# pre_pcb_new_pcb_design.net
KiCad netlist of a schematic drawn in EasyEDA Pro
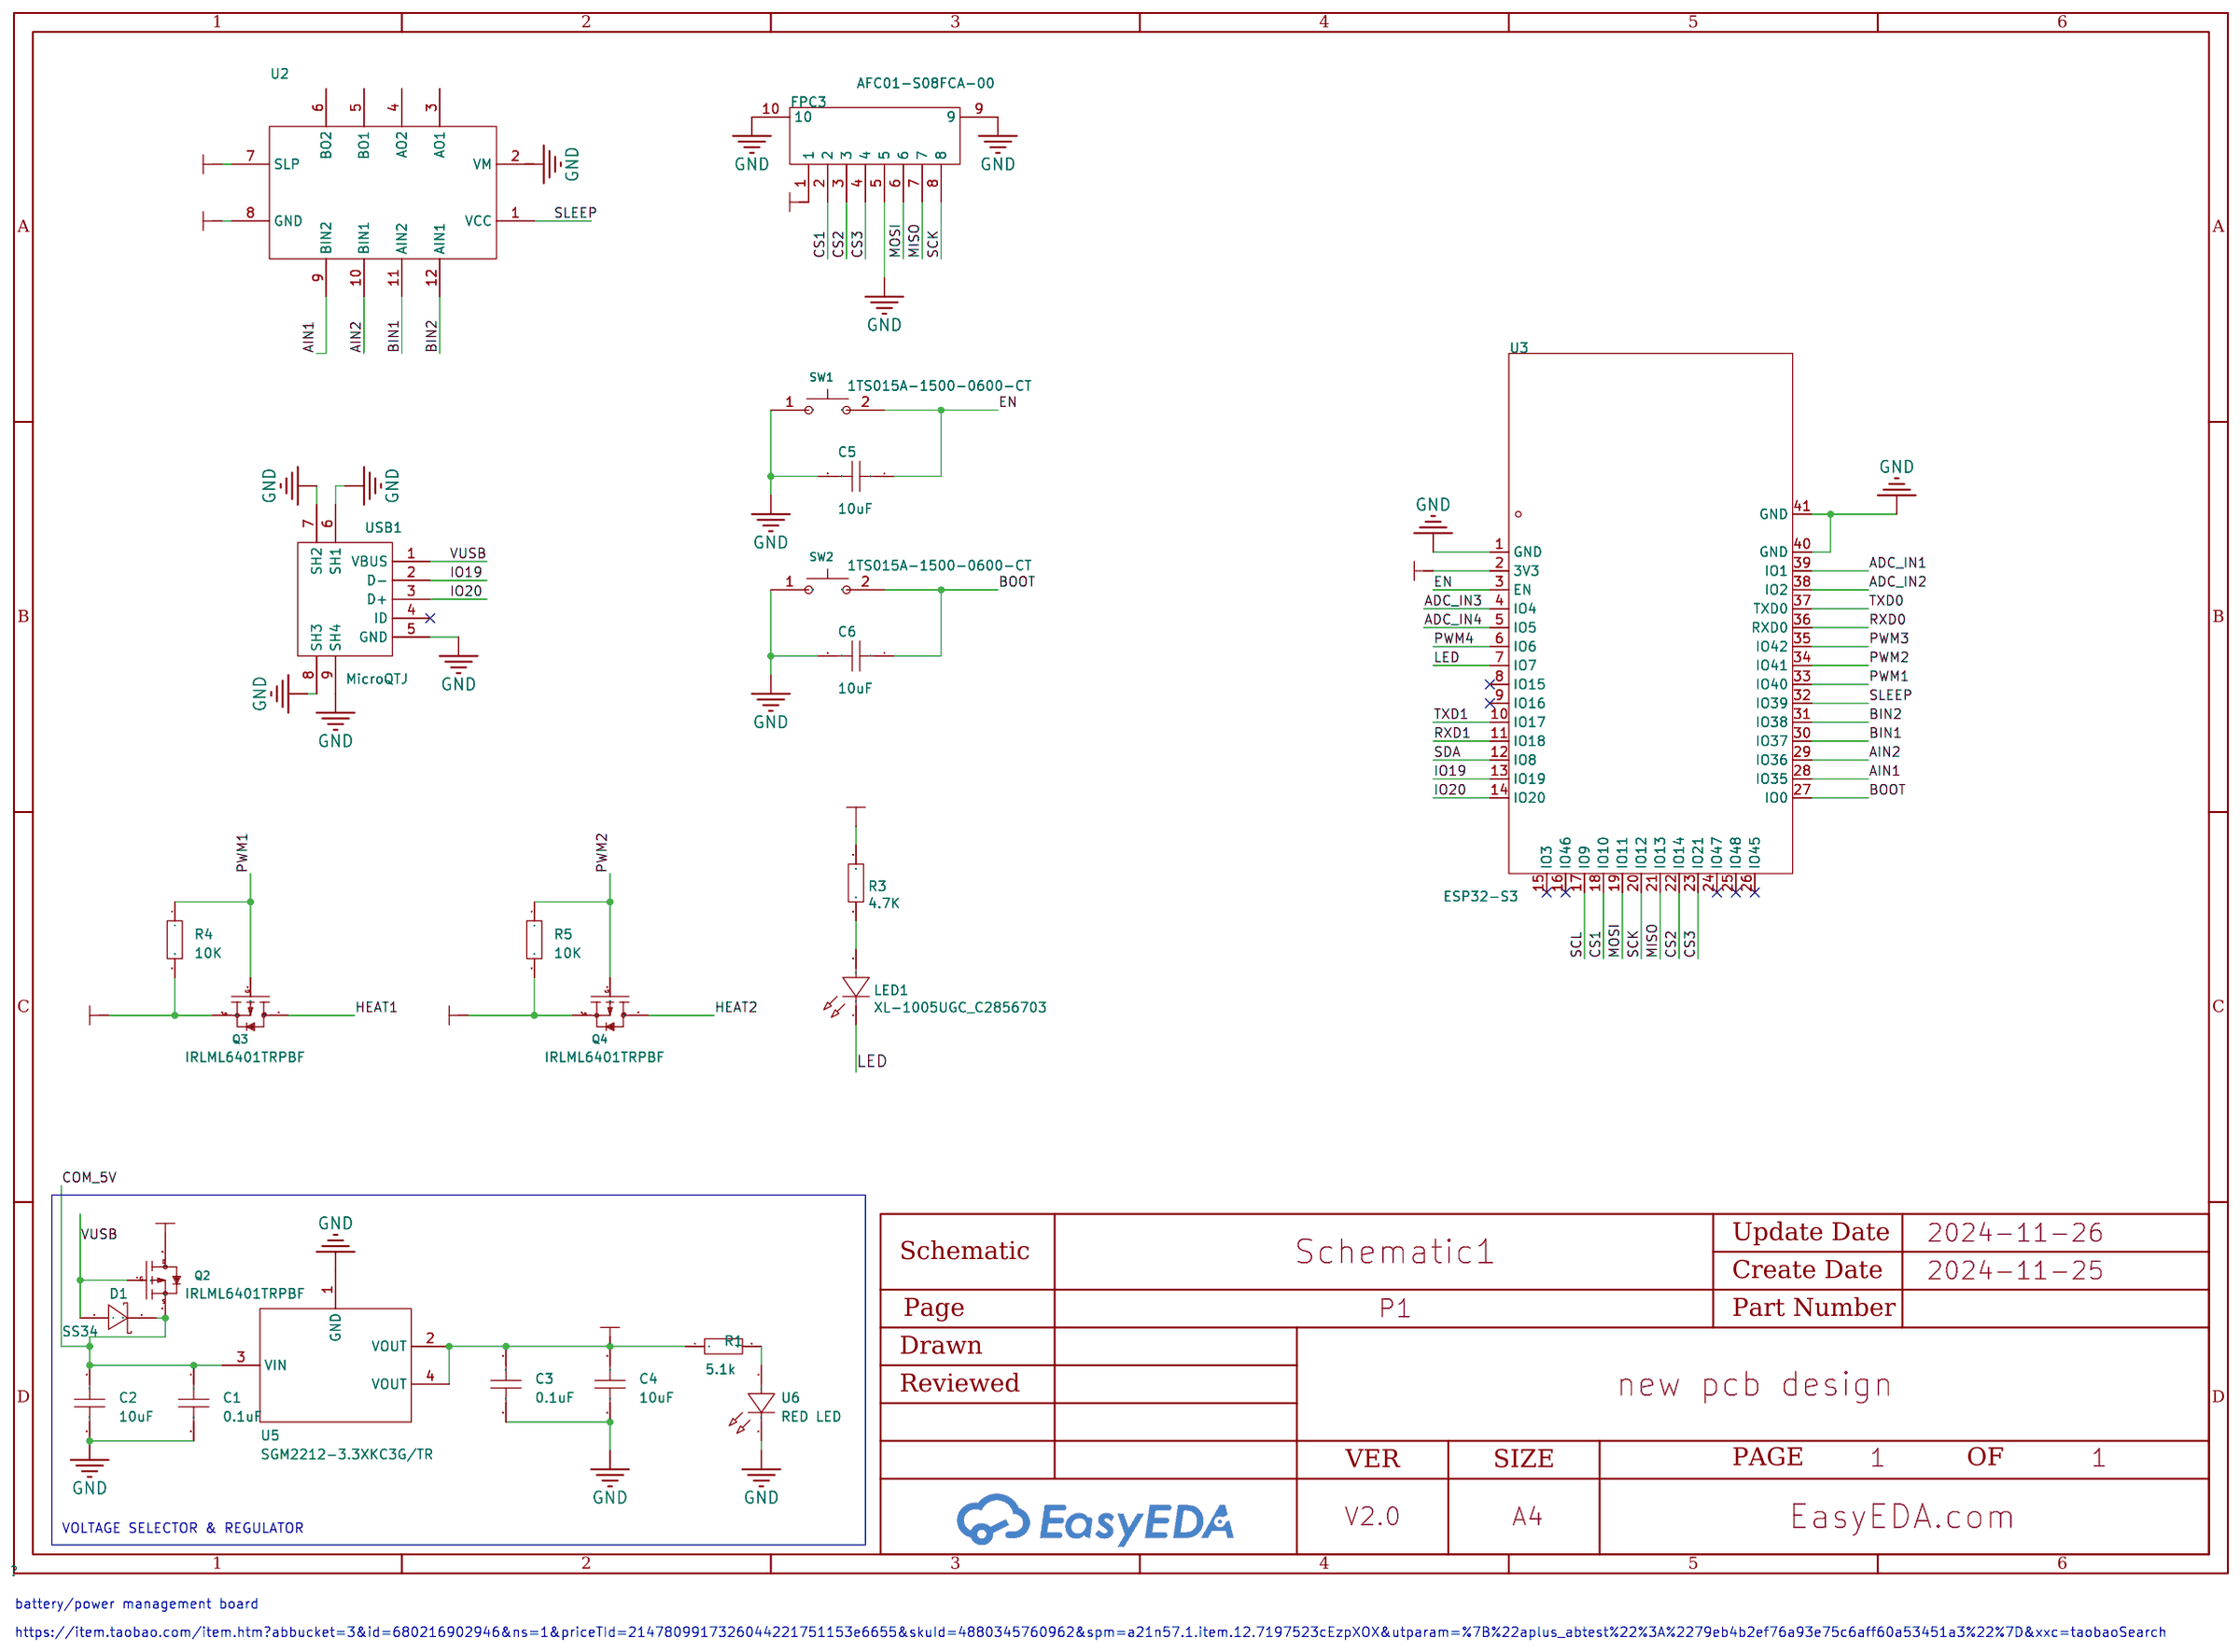
[diagram p0: schematic sheet]

(export (version "E")
  (design (tool "Eeschema 10.0.6"))
  (components
    (comp (ref "C1")
      (value "0.1uF")
      (footprint "easyedapro:C0603")
      (libsource (lib "easyedapro") (part "CAP"))
    )
    (comp (ref "C2")
      (value "10uF")
      (footprint "easyedapro:C0603")
      (libsource (lib "easyedapro") (part "CAP"))
    )
    (comp (ref "C3")
      (value "0.1uF")
      (footprint "easyedapro:C0603")
      (libsource (lib "easyedapro") (part "CAP"))
    )
    (comp (ref "C4")
      (value "10uF")
      (footprint "easyedapro:C0603")
      (libsource (lib "easyedapro") (part "CAP"))
    )
    (comp (ref "C5")
      (value "10uF")
      (footprint "easyedapro:C0603")
      (libsource (lib "easyedapro") (part "CAP"))
    )
    (comp (ref "C6")
      (value "10uF")
      (footprint "easyedapro:C0603")
      (libsource (lib "easyedapro") (part "CAP"))
    )
    (comp (ref "D1")
      (value "SS34")
      (footprint "easyedapro:SMC_L6.9-W5.9-LS7.9-RD")
      (description "Forward Voltage (Vf@If):500mV@3A Reverse Voltage (Vr):40V Average Rectified Current (Io):3A")
      (libsource (lib "easyedapro") (part "SS34_C169162"))
    )
    (comp (ref "FPC3")
      (value "AFC01-S08FCA-00")
      (footprint "easyedapro:FPC-SMD_P0.50-8P_FGS-XJ-H2.0")
      (fields (field (name "Manufacturer") "JS(钜硕电子)"))
      (libsource (lib "easyedapro") (part "AFC01-S08FCA-00"))
    )
    (comp (ref "LED1")
      (value "XL-1005UGC_C2856703")
      (footprint "easyedapro:LED0402-RD_GREEN")
      (fields (field (name "Manufacturer Part") "XL-1005UGC") (field (name "Manufacturer") "XINGLIGHT(成兴光)"))
      (libsource (lib "easyedapro") (part "XL-1005UGC_C2856703"))
    )
    (comp (ref "Q2")
      (value "IRLML6401TRPBF")
      (footprint "easyedapro:SOT-23-3_L2.9-W1.3-P1.90-LS2.4-BR")
      (fields (field (name "Manufacturer") "TECH PUBLIC(台舟)"))
      (libsource (lib "easyedapro") (part "IRLML6401TRPBF_C5182042"))
    )
    (comp (ref "Q3")
      (value "IRLML6401TRPBF")
      (footprint "easyedapro:SOT-23-3_L2.9-W1.3-P1.90-LS2.4-BR")
      (fields (field (name "Manufacturer") "TECH PUBLIC(台舟)"))
      (libsource (lib "easyedapro") (part "IRLML6401TRPBF_C5182042"))
    )
    (comp (ref "Q4")
      (value "IRLML6401TRPBF")
      (footprint "easyedapro:SOT-23-3_L2.9-W1.3-P1.90-LS2.4-BR")
      (fields (field (name "Manufacturer") "TECH PUBLIC(台舟)"))
      (libsource (lib "easyedapro") (part "IRLML6401TRPBF_C5182042"))
    )
    (comp (ref "R1")
      (value "5.1k")
      (footprint "easyedapro:R0603")
      (libsource (lib "easyedapro") (part "Res"))
    )
    (comp (ref "R3")
      (value "4.7K")
      (footprint "easyedapro:R0402")
      (fields (field (name "Manufacturer Part") "RC0402FR-0710KL") (field (name "Manufacturer") "YAGEO(国巨)"))
      (libsource (lib "easyedapro") (part "4.7K"))
    )
    (comp (ref "R4") (value "10K") (footprint "easyedapro:R0603") (libsource (lib "easyedapro") (part "Res")))
    (comp (ref "R5") (value "10K") (footprint "easyedapro:R0603") (libsource (lib "easyedapro") (part "Res")))
    (comp (ref "SW1")
      (value "1TS015A-1500-0600-CT")
      (footprint "easyedapro:SW-SMD_L3.0-W2.0-LS3.5")
      (fields (field (name "Manufacturer") "HYP(鸿源精密)"))
      (libsource (lib "easyedapro") (part "1TS015A-1500-0600-CT"))
    )
    (comp (ref "SW2")
      (value "1TS015A-1500-0600-CT")
      (footprint "easyedapro:SW-SMD_L3.0-W2.0-LS3.5")
      (fields (field (name "Manufacturer") "HYP(鸿源精密)"))
      (libsource (lib "easyedapro") (part "1TS015A-1500-0600-CT"))
    )
    (comp (ref "U2")
      (value "~")
      (footprint "easyedapro:DOUBLE_DRV8210")
      (libsource (lib "easyedapro") (part "DOUBLE_DRV8210"))
    )
    (comp (ref "U3")
      (value "ESP32-S3")
      (footprint "easyedapro:WIRELM-SMD_ESP32-S3-WROOM-1")
      (description "Core Processor:ESP32-S3 Chip Support Interface:I2C；GPIO；SPI；PWM；ADC；UART；USB；I2S Frequency:2.4GHz")
      (fields
        (field (name "Manufacturer Part") "ESP32-S3-WROOM-1-N8R2")
        (field (name "Manufacturer") "ESPRESSIF(乐鑫)")
      )
      (libsource (lib "easyedapro") (part "ESP32-S3-WROOM-1(N8R2)"))
    )
    (comp (ref "U5")
      (value "SGM2212-3.3XKC3G/TR")
      (footprint "easyedapro:SOT-223-4_L6.5-W3.5-P2.30-LS7.0-BR")
      (libsource (lib "easyedapro") (part "SGM2212-3.3XKC3G/TR"))
    )
    (comp (ref "U6")
      (value "RED LED")
      (footprint "easyedapro:LED0402-R-RD")
      (fields (field (name "Manufacturer") "YONGYUTAI(永裕泰)"))
      (libsource (lib "easyedapro") (part "YLED0402G"))
    )
    (comp (ref "USB1")
      (value "MicroQTJ")
      (footprint "easyedapro:MICRO-USB-SMD_MICROQTJ-5P")
      (fields (field (name "Manufacturer") "SHOU HAN(首韩)"))
      (libsource (lib "easyedapro") (part "MICROQTJ"))
    )
  )
  (nets
    (net (code "1") (name "/ADC_IN1") (class "Default")
      (node (ref "U3") (pin "39") (pinfunction "IO1_39") (pintype "unspecified"))
    )
    (net (code "2") (name "/ADC_IN2") (class "Default")
      (node (ref "U3") (pin "38") (pinfunction "IO2_38") (pintype "unspecified"))
    )
    (net (code "3") (name "/ADC_IN3") (class "Default")
      (node (ref "U3") (pin "4") (pinfunction "IO4_4") (pintype "unspecified"))
    )
    (net (code "4") (name "/ADC_IN4") (class "Default")
      (node (ref "U3") (pin "5") (pinfunction "IO5_5") (pintype "unspecified"))
    )
    (net (code "5") (name "/AIN1") (class "Default")
      (node (ref "U2") (pin "9") (pinfunction "BIN2_9") (pintype "input"))
      (node (ref "U3") (pin "28") (pinfunction "IO35_28") (pintype "unspecified"))
    )
    (net (code "6") (name "/AIN2") (class "Default")
      (node (ref "U2") (pin "10") (pinfunction "BIN1_10") (pintype "input"))
      (node (ref "U3") (pin "29") (pinfunction "IO36_29") (pintype "unspecified"))
    )
    (net (code "7") (name "/BIN1") (class "Default")
      (node (ref "U2") (pin "11") (pinfunction "AIN2_11") (pintype "input"))
      (node (ref "U3") (pin "30") (pinfunction "IO37_30") (pintype "unspecified"))
    )
    (net (code "8") (name "/BIN2") (class "Default")
      (node (ref "U2") (pin "12") (pinfunction "AIN1_12") (pintype "input"))
      (node (ref "U3") (pin "31") (pinfunction "IO38_31") (pintype "unspecified"))
    )
    (net (code "9") (name "/BOOT") (class "Default")
      (node (ref "C6") (pin "1") (pinfunction "1_1") (pintype "input"))
      (node (ref "SW2") (pin "2") (pinfunction "2_2") (pintype "input"))
      (node (ref "U3") (pin "27") (pinfunction "IO0_27") (pintype "unspecified"))
    )
    (net (code "10") (name "/COM_5V") (class "Default")
      (node (ref "C1") (pin "1") (pinfunction "1_1") (pintype "input"))
      (node (ref "C2") (pin "1") (pinfunction "1_1") (pintype "input"))
      (node (ref "D1") (pin "1") (pinfunction "C_1") (pintype "input"))
      (node (ref "Q2") (pin "2") (pinfunction "S_2") (pintype "input"))
      (node (ref "U5") (pin "3") (pinfunction "VIN_3") (pintype "unspecified"))
    )
    (net (code "11") (name "/CS1") (class "Default")
      (node (ref "FPC3") (pin "2") (pinfunction "2_2") (pintype "unspecified"))
      (node (ref "U3") (pin "18") (pinfunction "IO10_18") (pintype "unspecified"))
    )
    (net (code "12") (name "/CS2") (class "Default")
      (node (ref "FPC3") (pin "3") (pinfunction "3_3") (pintype "unspecified"))
      (node (ref "U3") (pin "22") (pinfunction "IO14_22") (pintype "unspecified"))
    )
    (net (code "13") (name "/CS3") (class "Default")
      (node (ref "FPC3") (pin "4") (pinfunction "4_4") (pintype "unspecified"))
      (node (ref "U3") (pin "23") (pinfunction "IO21_23") (pintype "unspecified"))
    )
    (net (code "14") (name "/EN") (class "Default")
      (node (ref "C5") (pin "1") (pinfunction "1_1") (pintype "input"))
      (node (ref "SW1") (pin "2") (pinfunction "2_2") (pintype "input"))
      (node (ref "U3") (pin "3") (pinfunction "EN_3") (pintype "unspecified"))
    )
    (net (code "15") (name "/HEAT1") (class "Default")
      (node (ref "Q3") (pin "3") (pinfunction "D_3") (pintype "input"))
    )
    (net (code "16") (name "/HEAT2") (class "Default")
      (node (ref "Q4") (pin "3") (pinfunction "D_3") (pintype "input"))
    )
    (net (code "17") (name "/IO19") (class "Default")
      (node (ref "U3") (pin "13") (pinfunction "IO19_13") (pintype "unspecified"))
      (node (ref "USB1") (pin "2") (pinfunction "D-_2") (pintype "unspecified"))
    )
    (net (code "18") (name "/IO20") (class "Default")
      (node (ref "U3") (pin "14") (pinfunction "IO20_14") (pintype "unspecified"))
      (node (ref "USB1") (pin "3") (pinfunction "D+_3") (pintype "unspecified"))
    )
    (net (code "19") (name "/LED") (class "Default")
      (node (ref "LED1") (pin "1") (pinfunction "K_1") (pintype "unspecified"))
      (node (ref "U3") (pin "7") (pinfunction "IO7_7") (pintype "unspecified"))
    )
    (net (code "20") (name "/MISO") (class "Default")
      (node (ref "FPC3") (pin "7") (pinfunction "7_7") (pintype "unspecified"))
      (node (ref "U3") (pin "21") (pinfunction "IO13_21") (pintype "unspecified"))
    )
    (net (code "21") (name "/MOSI") (class "Default")
      (node (ref "FPC3") (pin "6") (pinfunction "6_6") (pintype "unspecified"))
      (node (ref "U3") (pin "19") (pinfunction "IO11_19") (pintype "unspecified"))
    )
    (net (code "22") (name "/PWM1") (class "Default")
      (node (ref "Q3") (pin "1") (pinfunction "G_1") (pintype "input"))
      (node (ref "R4") (pin "1") (pinfunction "1_1") (pintype "input"))
      (node (ref "U3") (pin "33") (pinfunction "IO40_33") (pintype "unspecified"))
    )
    (net (code "23") (name "/PWM2") (class "Default")
      (node (ref "Q4") (pin "1") (pinfunction "G_1") (pintype "input"))
      (node (ref "R5") (pin "1") (pinfunction "1_1") (pintype "input"))
      (node (ref "U3") (pin "34") (pinfunction "IO41_34") (pintype "unspecified"))
    )
    (net (code "24") (name "/PWM3") (class "Default")
      (node (ref "U3") (pin "35") (pinfunction "IO42_35") (pintype "unspecified"))
    )
    (net (code "25") (name "/PWM4") (class "Default")
      (node (ref "U3") (pin "6") (pinfunction "IO6_6") (pintype "unspecified"))
    )
    (net (code "26") (name "/RXD0") (class "Default")
      (node (ref "U3") (pin "36") (pinfunction "RXD0_36") (pintype "unspecified"))
    )
    (net (code "27") (name "/RXD1") (class "Default")
      (node (ref "U3") (pin "11") (pinfunction "IO18_11") (pintype "unspecified"))
    )
    (net (code "28") (name "/SCK") (class "Default")
      (node (ref "FPC3") (pin "8") (pinfunction "8_8") (pintype "unspecified"))
      (node (ref "U3") (pin "20") (pinfunction "IO12_20") (pintype "unspecified"))
    )
    (net (code "29") (name "/SCL") (class "Default")
      (node (ref "U3") (pin "17") (pinfunction "IO9_17") (pintype "unspecified"))
    )
    (net (code "30") (name "/SDA") (class "Default")
      (node (ref "U3") (pin "12") (pinfunction "IO8_12") (pintype "unspecified"))
    )
    (net (code "31") (name "/SLEEP") (class "Default")
      (node (ref "U2") (pin "1") (pinfunction "VCC_1") (pintype "input"))
      (node (ref "U3") (pin "32") (pinfunction "IO39_32") (pintype "unspecified"))
    )
    (net (code "32") (name "/TXD0") (class "Default")
      (node (ref "U3") (pin "37") (pinfunction "TXD0_37") (pintype "unspecified"))
    )
    (net (code "33") (name "/TXD1") (class "Default")
      (node (ref "U3") (pin "10") (pinfunction "IO17_10") (pintype "unspecified"))
    )
    (net (code "34") (name "/VUSB") (class "Default")
      (node (ref "D1") (pin "2") (pinfunction "A_2") (pintype "input"))
      (node (ref "Q2") (pin "1") (pinfunction "G_1") (pintype "input"))
      (node (ref "USB1") (pin "1") (pinfunction "VBUS_1") (pintype "unspecified"))
    )
    (net (code "35") (name "3V3") (class "Default")
      (node (ref "R3") (pin "1") (pinfunction "1_1") (pintype "input"))
    )
    (net (code "36") (name "GND") (class "Default")
      (node (ref "C1") (pin "2") (pinfunction "2_2") (pintype "input"))
      (node (ref "C2") (pin "2") (pinfunction "2_2") (pintype "input"))
      (node (ref "C3") (pin "1") (pinfunction "1_1") (pintype "input"))
      (node (ref "C4") (pin "1") (pinfunction "1_1") (pintype "input"))
      (node (ref "C5") (pin "2") (pinfunction "2_2") (pintype "input"))
      (node (ref "C6") (pin "2") (pinfunction "2_2") (pintype "input"))
      (node (ref "FPC3") (pin "10") (pinfunction "10_10") (pintype "unspecified"))
      (node (ref "FPC3") (pin "5") (pinfunction "5_5") (pintype "unspecified"))
      (node (ref "FPC3") (pin "9") (pinfunction "9_9") (pintype "unspecified"))
      (node (ref "SW1") (pin "1") (pinfunction "1_1") (pintype "input"))
      (node (ref "SW2") (pin "1") (pinfunction "1_1") (pintype "input"))
      (node (ref "U2") (pin "2") (pinfunction "VM_2") (pintype "input"))
      (node (ref "U3") (pin "1") (pinfunction "GND_1") (pintype "unspecified"))
      (node (ref "U3") (pin "40") (pinfunction "GND_40") (pintype "unspecified"))
      (node (ref "U3") (pin "41") (pinfunction "GND_41") (pintype "unspecified"))
      (node (ref "U5") (pin "1") (pinfunction "GND_1") (pintype "unspecified"))
      (node (ref "U6") (pin "2") (pinfunction "K_2") (pintype "unspecified"))
      (node (ref "USB1") (pin "5") (pinfunction "GND_5") (pintype "unspecified"))
      (node (ref "USB1") (pin "6") (pinfunction "SH1_6") (pintype "unspecified"))
      (node (ref "USB1") (pin "7") (pinfunction "SH2_7") (pintype "unspecified"))
      (node (ref "USB1") (pin "8") (pinfunction "SH3_8") (pintype "unspecified"))
      (node (ref "USB1") (pin "9") (pinfunction "SH4_9") (pintype "unspecified"))
    )
    (net (code "37") (name "Net-(LED1-A)") (class "Default")
      (node (ref "LED1") (pin "2") (pinfunction "A_2") (pintype "unspecified"))
      (node (ref "R3") (pin "2") (pinfunction "2_2") (pintype "input"))
    )
    (net (code "38") (name "Net-(U6-A)") (class "Default")
      (node (ref "R1") (pin "2") (pinfunction "2_2") (pintype "input"))
      (node (ref "U6") (pin "1") (pinfunction "A_1") (pintype "unspecified"))
    )
    (net (code "39") (name "VBAT") (class "Default")
      (node (ref "Q2") (pin "3") (pinfunction "D_3") (pintype "input"))
    )
    (net (code "40") (name "VCC_3V3") (class "Default")
      (node (ref "C3") (pin "2") (pinfunction "2_2") (pintype "input"))
      (node (ref "C4") (pin "2") (pinfunction "2_2") (pintype "input"))
      (node (ref "FPC3") (pin "1") (pinfunction "1_1") (pintype "unspecified"))
      (node (ref "R1") (pin "1") (pinfunction "1_1") (pintype "input"))
      (node (ref "U2") (pin "7") (pinfunction "SLP_7") (pintype "input"))
      (node (ref "U3") (pin "2") (pinfunction "3V3_2") (pintype "unspecified"))
      (node (ref "U5") (pin "2") (pinfunction "VOUT_2") (pintype "unspecified"))
      (node (ref "U5") (pin "4") (pinfunction "VOUT_4") (pintype "unspecified"))
    )
    (net (code "41") (name "VM") (class "Default")
      (node (ref "Q3") (pin "2") (pinfunction "S_2") (pintype "input"))
      (node (ref "Q4") (pin "2") (pinfunction "S_2") (pintype "input"))
      (node (ref "R4") (pin "2") (pinfunction "2_2") (pintype "input"))
      (node (ref "R5") (pin "2") (pinfunction "2_2") (pintype "input"))
      (node (ref "U2") (pin "8") (pinfunction "GND_8") (pintype "input"))
    )
    (net (code "42") (name "unconnected-(U2-AO1-Pad3)") (class "Default")
      (node (ref "U2") (pin "3") (pinfunction "AO1_3") (pintype "input"))
    )
    (net (code "43") (name "unconnected-(U2-AO2-Pad4)") (class "Default")
      (node (ref "U2") (pin "4") (pinfunction "AO2_4") (pintype "input"))
    )
    (net (code "44") (name "unconnected-(U2-BO1-Pad5)") (class "Default")
      (node (ref "U2") (pin "5") (pinfunction "BO1_5") (pintype "input"))
    )
    (net (code "45") (name "unconnected-(U2-BO2-Pad6)") (class "Default")
      (node (ref "U2") (pin "6") (pinfunction "BO2_6") (pintype "input"))
    )
    (net (code "46") (name "unconnected-(U3-IO3-Pad15)") (class "Default")
      (node (ref "U3") (pin "15") (pinfunction "IO3_15") (pintype "unspecified+no_connect"))
    )
    (net (code "47") (name "unconnected-(U3-IO15-Pad8)") (class "Default")
      (node (ref "U3") (pin "8") (pinfunction "IO15_8") (pintype "unspecified+no_connect"))
    )
    (net (code "48") (name "unconnected-(U3-IO16-Pad9)") (class "Default")
      (node (ref "U3") (pin "9") (pinfunction "IO16_9") (pintype "unspecified+no_connect"))
    )
    (net (code "49") (name "unconnected-(U3-IO45-Pad26)") (class "Default")
      (node (ref "U3") (pin "26") (pinfunction "IO45_26") (pintype "unspecified+no_connect"))
    )
    (net (code "50") (name "unconnected-(U3-IO46-Pad16)") (class "Default")
      (node (ref "U3") (pin "16") (pinfunction "IO46_16") (pintype "unspecified+no_connect"))
    )
    (net (code "51") (name "unconnected-(U3-IO47-Pad24)") (class "Default")
      (node (ref "U3") (pin "24") (pinfunction "IO47_24") (pintype "unspecified+no_connect"))
    )
    (net (code "52") (name "unconnected-(U3-IO48-Pad25)") (class "Default")
      (node (ref "U3") (pin "25") (pinfunction "IO48_25") (pintype "unspecified+no_connect"))
    )
    (net (code "53") (name "unconnected-(USB1-ID-Pad4)") (class "Default")
      (node (ref "USB1") (pin "4") (pinfunction "ID_4") (pintype "unspecified+no_connect"))
    )
  )
)
